# pcie_board.net
KiCad netlist of a schematic drawn in EAGLE
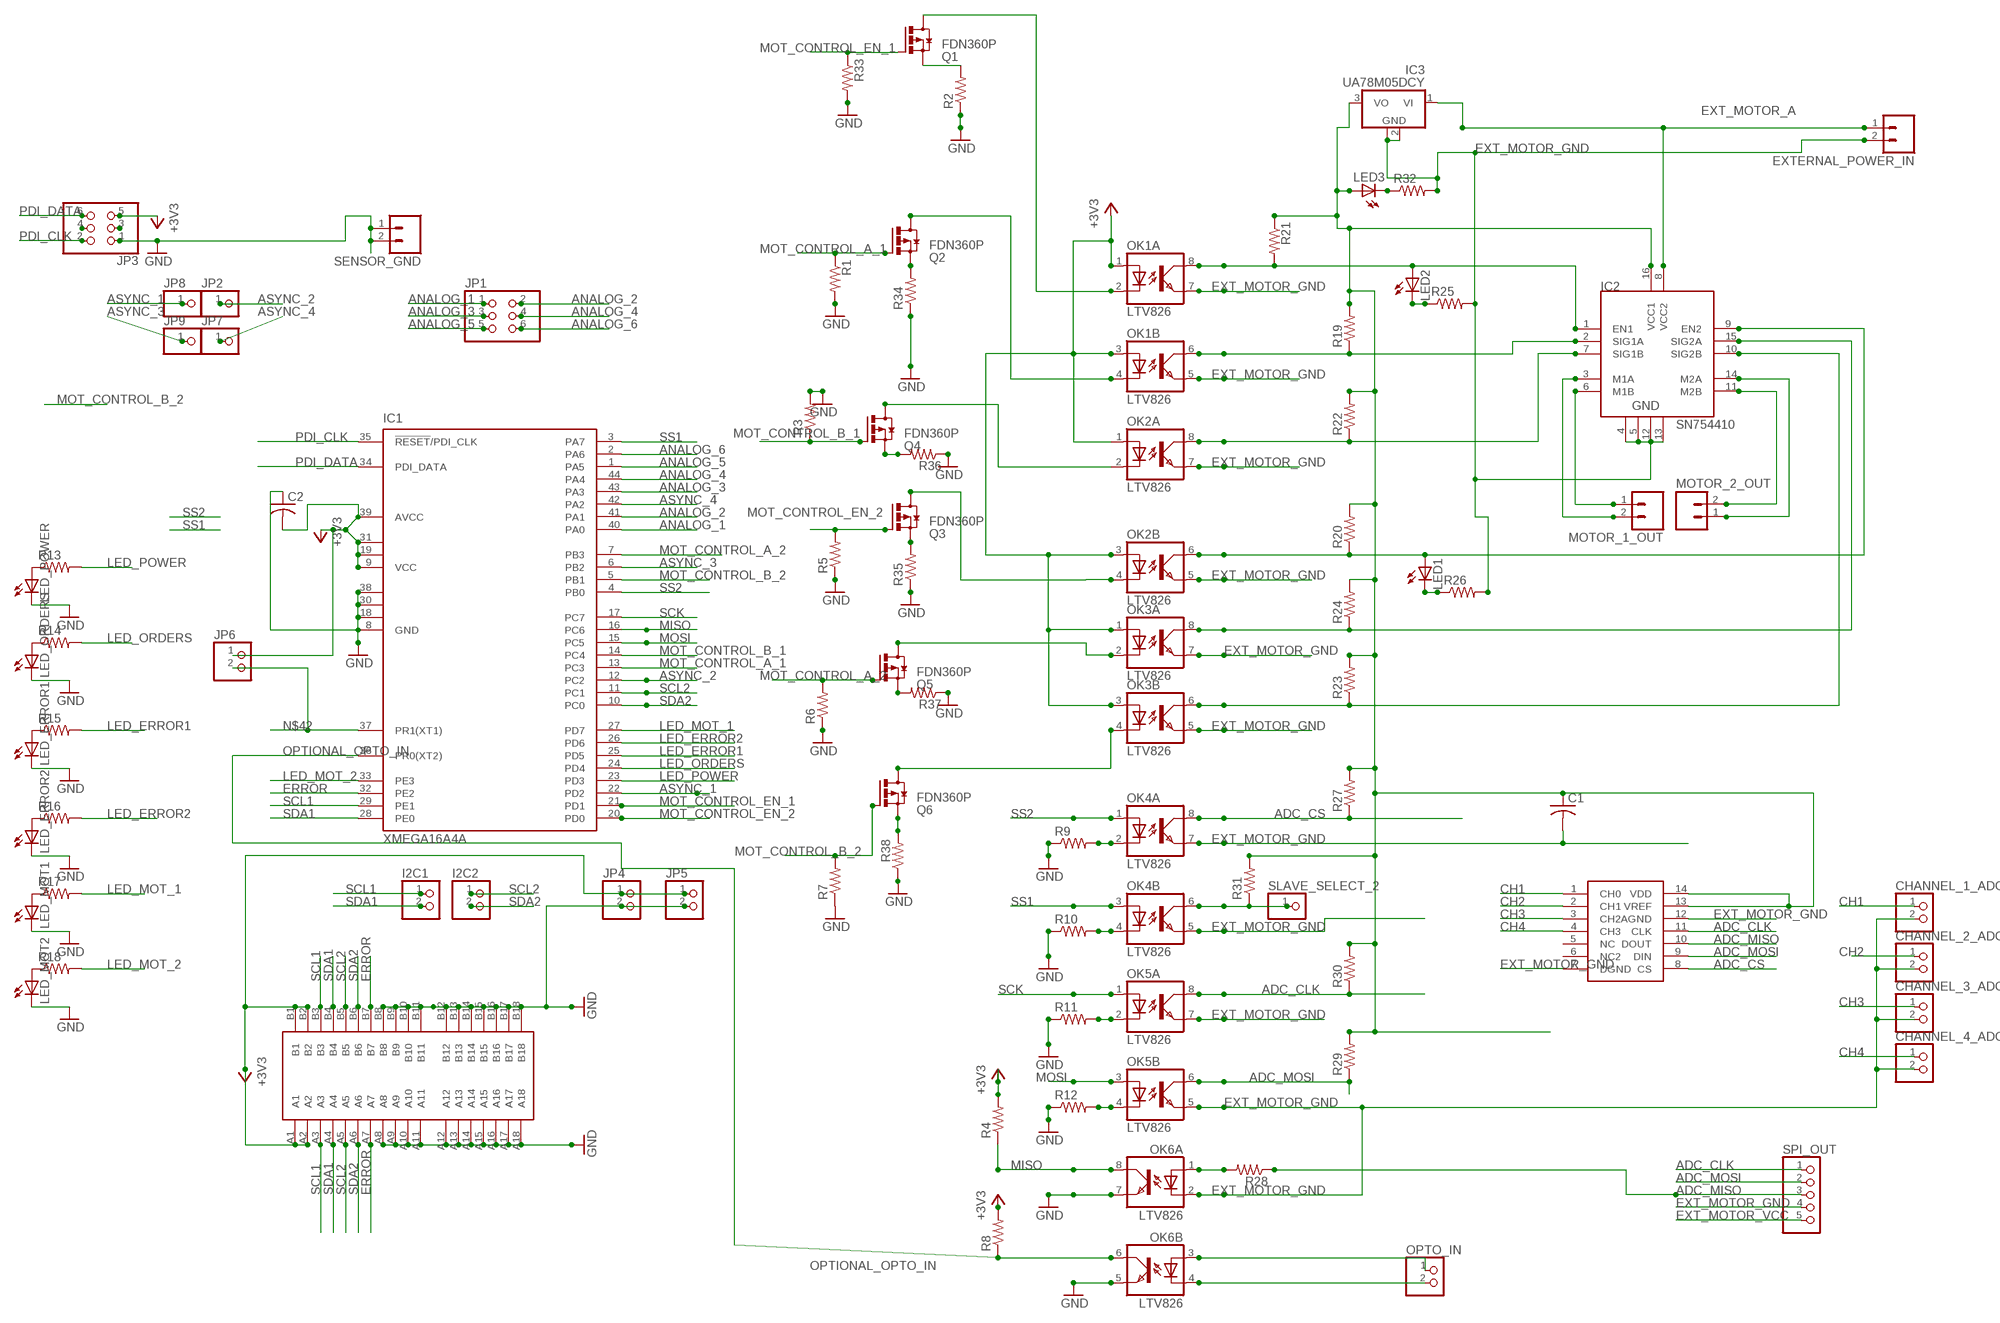
[diagram p0: schematic, sheet 1]

(export (version "E")
  (design (tool "Eeschema 10.0.6"))
  (components
    (comp (ref "C1")
      (value "C-US025-040X050")
      (footprint "eagle-import:C025-040X050")
      (libsource (lib "eagle-import") (part "C-US025-040X050"))
    )
    (comp (ref "C2")
      (value "C-US025-040X050")
      (footprint "eagle-import:C025-040X050")
      (libsource (lib "eagle-import") (part "C-US025-040X050"))
    )
    (comp (ref "CHANNEL_1_ADC")
      (value "PINHD-1X2")
      (footprint "eagle-import:1X02")
      (libsource (lib "eagle-import") (part "PINHD-1X2"))
    )
    (comp (ref "CHANNEL_2_ADC")
      (value "PINHD-1X2")
      (footprint "eagle-import:1X02")
      (libsource (lib "eagle-import") (part "PINHD-1X2"))
    )
    (comp (ref "CHANNEL_3_ADC")
      (value "PINHD-1X2")
      (footprint "eagle-import:1X02")
      (libsource (lib "eagle-import") (part "PINHD-1X2"))
    )
    (comp (ref "CHANNEL_4_ADC")
      (value "PINHD-1X2")
      (footprint "eagle-import:1X02")
      (libsource (lib "eagle-import") (part "PINHD-1X2"))
    )
    (comp (ref "EXTERNAL_POWER_IN")
      (value "M023.5MM")
      (footprint "eagle-import:SCREWTERMINAL-3.5MM-2")
      (libsource (lib "eagle-import") (part "M023.5MM"))
    )
    (comp (ref "I2C1")
      (value "PINHD-1X2")
      (footprint "eagle-import:1X02")
      (libsource (lib "eagle-import") (part "PINHD-1X2"))
    )
    (comp (ref "I2C2")
      (value "PINHD-1X2")
      (footprint "eagle-import:1X02")
      (libsource (lib "eagle-import") (part "PINHD-1X2"))
    )
    (comp (ref "IC1")
      (value "XMEGA16A4A")
      (footprint "eagle-import:TQFP44")
      (libsource (lib "eagle-import") (part "XMEGA16A4A"))
    )
    (comp (ref "IC2")
      (value "SN754410")
      (footprint "eagle-import:DIP16")
      (libsource (lib "eagle-import") (part "SN754410"))
    )
    (comp (ref "IC3")
      (value "UA78M05DCY")
      (footprint "eagle-import:SOT223")
      (libsource (lib "eagle-import") (part "UA78MDCY05"))
    )
    (comp (ref "JP1")
      (value "PINHD-2X3")
      (footprint "eagle-import:2X03")
      (libsource (lib "eagle-import") (part "PINHD-2X3"))
    )
    (comp (ref "JP2")
      (value "PINHD-1X1")
      (footprint "eagle-import:1X01")
      (libsource (lib "eagle-import") (part "PINHD-1X1"))
    )
    (comp (ref "JP3")
      (value "PINHD-2X3")
      (footprint "eagle-import:2X03")
      (libsource (lib "eagle-import") (part "PINHD-2X3"))
    )
    (comp (ref "JP4")
      (value "PINHD-1X2")
      (footprint "eagle-import:1X02")
      (libsource (lib "eagle-import") (part "PINHD-1X2"))
    )
    (comp (ref "JP5")
      (value "PINHD-1X2")
      (footprint "eagle-import:1X02")
      (libsource (lib "eagle-import") (part "PINHD-1X2"))
    )
    (comp (ref "JP6")
      (value "PINHD-1X2")
      (footprint "eagle-import:1X02")
      (libsource (lib "eagle-import") (part "PINHD-1X2"))
    )
    (comp (ref "JP7")
      (value "PINHD-1X1")
      (footprint "eagle-import:1X01")
      (libsource (lib "eagle-import") (part "PINHD-1X1"))
    )
    (comp (ref "JP8")
      (value "PINHD-1X1")
      (footprint "eagle-import:1X01")
      (libsource (lib "eagle-import") (part "PINHD-1X1"))
    )
    (comp (ref "JP9")
      (value "PINHD-1X1")
      (footprint "eagle-import:1X01")
      (libsource (lib "eagle-import") (part "PINHD-1X1"))
    )
    (comp (ref "LED1")
      (value "LEDCHIP-LED0603")
      (footprint "eagle-import:CHIP-LED0603")
      (libsource (lib "eagle-import") (part "LEDCHIP-LED0603"))
    )
    (comp (ref "LED2")
      (value "LEDCHIP-LED0603")
      (footprint "eagle-import:CHIP-LED0603")
      (libsource (lib "eagle-import") (part "LEDCHIP-LED0603"))
    )
    (comp (ref "LED3")
      (value "LEDCHIP-LED0603")
      (footprint "eagle-import:CHIP-LED0603")
      (libsource (lib "eagle-import") (part "LEDCHIP-LED0603"))
    )
    (comp (ref "LED_ERROR1")
      (value "LED5MM")
      (footprint "eagle-import:LED5MM")
      (libsource (lib "eagle-import") (part "LED5MM"))
    )
    (comp (ref "LED_ERROR2")
      (value "LED5MM")
      (footprint "eagle-import:LED5MM")
      (libsource (lib "eagle-import") (part "LED5MM"))
    )
    (comp (ref "LED_MOT1")
      (value "LED5MM")
      (footprint "eagle-import:LED5MM")
      (libsource (lib "eagle-import") (part "LED5MM"))
    )
    (comp (ref "LED_MOT2")
      (value "LED5MM")
      (footprint "eagle-import:LED5MM")
      (libsource (lib "eagle-import") (part "LED5MM"))
    )
    (comp (ref "LED_ORDERS")
      (value "LED5MM")
      (footprint "eagle-import:LED5MM")
      (libsource (lib "eagle-import") (part "LED5MM"))
    )
    (comp (ref "LED_POWER")
      (value "LED5MM")
      (footprint "eagle-import:LED5MM")
      (libsource (lib "eagle-import") (part "LED5MM"))
    )
    (comp (ref "MOTOR_1_OUT")
      (value "M023.5MM")
      (footprint "eagle-import:SCREWTERMINAL-3.5MM-2")
      (libsource (lib "eagle-import") (part "M023.5MM"))
    )
    (comp (ref "MOTOR_2_OUT")
      (value "M023.5MM")
      (footprint "eagle-import:SCREWTERMINAL-3.5MM-2")
      (libsource (lib "eagle-import") (part "M023.5MM"))
    )
    (comp (ref "OK1")
      (value "LTV826")
      (footprint "eagle-import:DIL08")
      (libsource (lib "eagle-import") (part "LTV826"))
    )
    (comp (ref "OK2")
      (value "LTV826")
      (footprint "eagle-import:DIL08")
      (libsource (lib "eagle-import") (part "LTV826"))
    )
    (comp (ref "OK3")
      (value "LTV826")
      (footprint "eagle-import:DIL08")
      (libsource (lib "eagle-import") (part "LTV826"))
    )
    (comp (ref "OK4")
      (value "LTV826")
      (footprint "eagle-import:DIL08")
      (libsource (lib "eagle-import") (part "LTV826"))
    )
    (comp (ref "OK5")
      (value "LTV826")
      (footprint "eagle-import:DIL08")
      (libsource (lib "eagle-import") (part "LTV826"))
    )
    (comp (ref "OK6")
      (value "LTV826")
      (footprint "eagle-import:DIL08")
      (libsource (lib "eagle-import") (part "LTV826"))
    )
    (comp (ref "OPTO_IN")
      (value "PINHD-1X2")
      (footprint "eagle-import:1X02")
      (libsource (lib "eagle-import") (part "PINHD-1X2"))
    )
    (comp (ref "Q1")
      (value "FDN360P")
      (footprint "eagle-import:SUPER-SOT3")
      (libsource (lib "eagle-import") (part "FDN360P"))
    )
    (comp (ref "Q2")
      (value "FDN360P")
      (footprint "eagle-import:SUPER-SOT3")
      (libsource (lib "eagle-import") (part "FDN360P"))
    )
    (comp (ref "Q3")
      (value "FDN360P")
      (footprint "eagle-import:SUPER-SOT3")
      (libsource (lib "eagle-import") (part "FDN360P"))
    )
    (comp (ref "Q4")
      (value "FDN360P")
      (footprint "eagle-import:SUPER-SOT3")
      (libsource (lib "eagle-import") (part "FDN360P"))
    )
    (comp (ref "Q5")
      (value "FDN360P")
      (footprint "eagle-import:SUPER-SOT3")
      (libsource (lib "eagle-import") (part "FDN360P"))
    )
    (comp (ref "Q6")
      (value "FDN360P")
      (footprint "eagle-import:SUPER-SOT3")
      (libsource (lib "eagle-import") (part "FDN360P"))
    )
    (comp (ref "R1")
      (value "R-US_M0805")
      (footprint "eagle-import:M0805")
      (libsource (lib "eagle-import") (part "R-US_M0805"))
    )
    (comp (ref "R2")
      (value "R-US_M0805")
      (footprint "eagle-import:M0805")
      (libsource (lib "eagle-import") (part "R-US_M0805"))
    )
    (comp (ref "R3")
      (value "R-US_M0805")
      (footprint "eagle-import:M0805")
      (libsource (lib "eagle-import") (part "R-US_M0805"))
    )
    (comp (ref "R4")
      (value "R-US_M0805")
      (footprint "eagle-import:M0805")
      (libsource (lib "eagle-import") (part "R-US_M0805"))
    )
    (comp (ref "R5")
      (value "R-US_M0805")
      (footprint "eagle-import:M0805")
      (libsource (lib "eagle-import") (part "R-US_M0805"))
    )
    (comp (ref "R6")
      (value "R-US_M0805")
      (footprint "eagle-import:M0805")
      (libsource (lib "eagle-import") (part "R-US_M0805"))
    )
    (comp (ref "R7")
      (value "R-US_M0805")
      (footprint "eagle-import:M0805")
      (libsource (lib "eagle-import") (part "R-US_M0805"))
    )
    (comp (ref "R8")
      (value "R-US_M0805")
      (footprint "eagle-import:M0805")
      (libsource (lib "eagle-import") (part "R-US_M0805"))
    )
    (comp (ref "R9")
      (value "R-US_M0805")
      (footprint "eagle-import:M0805")
      (libsource (lib "eagle-import") (part "R-US_M0805"))
    )
    (comp (ref "R10")
      (value "R-US_M0805")
      (footprint "eagle-import:M0805")
      (libsource (lib "eagle-import") (part "R-US_M0805"))
    )
    (comp (ref "R11")
      (value "R-US_M0805")
      (footprint "eagle-import:M0805")
      (libsource (lib "eagle-import") (part "R-US_M0805"))
    )
    (comp (ref "R12")
      (value "R-US_M0805")
      (footprint "eagle-import:M0805")
      (libsource (lib "eagle-import") (part "R-US_M0805"))
    )
    (comp (ref "R13")
      (value "R-US_M0805")
      (footprint "eagle-import:M0805")
      (libsource (lib "eagle-import") (part "R-US_M0805"))
    )
    (comp (ref "R14")
      (value "R-US_M0805")
      (footprint "eagle-import:M0805")
      (libsource (lib "eagle-import") (part "R-US_M0805"))
    )
    (comp (ref "R15")
      (value "R-US_M0805")
      (footprint "eagle-import:M0805")
      (libsource (lib "eagle-import") (part "R-US_M0805"))
    )
    (comp (ref "R16")
      (value "R-US_M0805")
      (footprint "eagle-import:M0805")
      (libsource (lib "eagle-import") (part "R-US_M0805"))
    )
    (comp (ref "R17")
      (value "R-US_M0805")
      (footprint "eagle-import:M0805")
      (libsource (lib "eagle-import") (part "R-US_M0805"))
    )
    (comp (ref "R18")
      (value "R-US_M0805")
      (footprint "eagle-import:M0805")
      (libsource (lib "eagle-import") (part "R-US_M0805"))
    )
    (comp (ref "R19")
      (value "R-US_M0805")
      (footprint "eagle-import:M0805")
      (libsource (lib "eagle-import") (part "R-US_M0805"))
    )
    (comp (ref "R20")
      (value "R-US_M0805")
      (footprint "eagle-import:M0805")
      (libsource (lib "eagle-import") (part "R-US_M0805"))
    )
    (comp (ref "R21")
      (value "R-US_M0805")
      (footprint "eagle-import:M0805")
      (libsource (lib "eagle-import") (part "R-US_M0805"))
    )
    (comp (ref "R22")
      (value "R-US_M0805")
      (footprint "eagle-import:M0805")
      (libsource (lib "eagle-import") (part "R-US_M0805"))
    )
    (comp (ref "R23")
      (value "R-US_M0805")
      (footprint "eagle-import:M0805")
      (libsource (lib "eagle-import") (part "R-US_M0805"))
    )
    (comp (ref "R24")
      (value "R-US_M0805")
      (footprint "eagle-import:M0805")
      (libsource (lib "eagle-import") (part "R-US_M0805"))
    )
    (comp (ref "R25")
      (value "R-US_M0805")
      (footprint "eagle-import:M0805")
      (libsource (lib "eagle-import") (part "R-US_M0805"))
    )
    (comp (ref "R26")
      (value "R-US_M0805")
      (footprint "eagle-import:M0805")
      (libsource (lib "eagle-import") (part "R-US_M0805"))
    )
    (comp (ref "R27")
      (value "R-US_M0805")
      (footprint "eagle-import:M0805")
      (libsource (lib "eagle-import") (part "R-US_M0805"))
    )
    (comp (ref "R28")
      (value "R-US_M0805")
      (footprint "eagle-import:M0805")
      (libsource (lib "eagle-import") (part "R-US_M0805"))
    )
    (comp (ref "R29")
      (value "R-US_M0805")
      (footprint "eagle-import:M0805")
      (libsource (lib "eagle-import") (part "R-US_M0805"))
    )
    (comp (ref "R30")
      (value "R-US_M0805")
      (footprint "eagle-import:M0805")
      (libsource (lib "eagle-import") (part "R-US_M0805"))
    )
    (comp (ref "R31")
      (value "R-US_M0805")
      (footprint "eagle-import:M0805")
      (libsource (lib "eagle-import") (part "R-US_M0805"))
    )
    (comp (ref "R32")
      (value "R-US_M0805")
      (footprint "eagle-import:M0805")
      (libsource (lib "eagle-import") (part "R-US_M0805"))
    )
    (comp (ref "R33")
      (value "R-US_M0805")
      (footprint "eagle-import:M0805")
      (libsource (lib "eagle-import") (part "R-US_M0805"))
    )
    (comp (ref "R34")
      (value "R-US_M0805")
      (footprint "eagle-import:M0805")
      (libsource (lib "eagle-import") (part "R-US_M0805"))
    )
    (comp (ref "R35")
      (value "R-US_M0805")
      (footprint "eagle-import:M0805")
      (libsource (lib "eagle-import") (part "R-US_M0805"))
    )
    (comp (ref "R36")
      (value "R-US_M0805")
      (footprint "eagle-import:M0805")
      (libsource (lib "eagle-import") (part "R-US_M0805"))
    )
    (comp (ref "R37")
      (value "R-US_M0805")
      (footprint "eagle-import:M0805")
      (libsource (lib "eagle-import") (part "R-US_M0805"))
    )
    (comp (ref "R38")
      (value "R-US_M0805")
      (footprint "eagle-import:M0805")
      (libsource (lib "eagle-import") (part "R-US_M0805"))
    )
    (comp (ref "SENSOR_GND")
      (value "M023.5MM")
      (footprint "eagle-import:SCREWTERMINAL-3.5MM-2")
      (libsource (lib "eagle-import") (part "M023.5MM"))
    )
    (comp (ref "SLAVE_SELECT_2")
      (value "PINHD-1X1")
      (footprint "eagle-import:1X01")
      (libsource (lib "eagle-import") (part "PINHD-1X1"))
    )
    (comp (ref "SPI_OUT")
      (value "PINHD-1X5")
      (footprint "eagle-import:1X05")
      (libsource (lib "eagle-import") (part "PINHD-1X5"))
    )
    (comp (ref "U$1")
      (value "PCI-E1X_EDGE")
      (footprint "eagle-import:PCI-E_X1_EDGE")
      (libsource (lib "eagle-import") (part "PCI-E1X_EDGE"))
    )
    (comp (ref "U$2")
      (value "MCP3004")
      (footprint "eagle-import:DIL14")
      (libsource (lib "eagle-import") (part "MCP3004"))
    )
  )
  (nets
    (net (code "1") (name "+3V3") (class "Default")
      (node (ref "C2") (pin "2") (pinfunction "2_2") (pintype "passive"))
      (node (ref "IC1") (pin "19") (pinfunction "VCC1_19") (pintype "power_in"))
      (node (ref "IC1") (pin "31") (pinfunction "VCC2_31") (pintype "power_in"))
      (node (ref "IC1") (pin "39") (pinfunction "AVCC_39") (pintype "power_in"))
      (node (ref "IC1") (pin "9") (pinfunction "VCC_9") (pintype "power_in"))
      (node (ref "JP3") (pin "5") (pinfunction "5_5") (pintype "passive"))
      (node (ref "JP4") (pin "1") (pinfunction "1_1") (pintype "passive"))
      (node (ref "JP5") (pin "1") (pinfunction "1_1") (pintype "passive"))
      (node (ref "JP6") (pin "1") (pinfunction "1_1") (pintype "passive"))
      (node (ref "OK1") (pin "1") (pinfunction "A_1") (pintype "passive"))
      (node (ref "OK1") (pin "3") (pinfunction "A_3") (pintype "passive"))
      (node (ref "OK2") (pin "1") (pinfunction "A_1") (pintype "passive"))
      (node (ref "OK2") (pin "3") (pinfunction "A_3") (pintype "passive"))
      (node (ref "OK3") (pin "1") (pinfunction "A_1") (pintype "passive"))
      (node (ref "OK3") (pin "3") (pinfunction "A_3") (pintype "passive"))
      (node (ref "R4") (pin "2") (pinfunction "2_2") (pintype "passive"))
      (node (ref "R8") (pin "2") (pinfunction "2_2") (pintype "passive"))
      (node (ref "U$1") (pin "A1") (pinfunction "A1_A1") (pintype "bidirectional"))
      (node (ref "U$1") (pin "A2") (pinfunction "A2_A2") (pintype "bidirectional"))
      (node (ref "U$1") (pin "B1") (pinfunction "B1_B1") (pintype "bidirectional"))
      (node (ref "U$1") (pin "B2") (pinfunction "B2_B2") (pintype "bidirectional"))
    )
    (net (code "2") (name "ADC_CLK") (class "Default")
      (node (ref "OK5") (pin "8") (pinfunction "COL_8") (pintype "passive"))
      (node (ref "R30") (pin "1") (pinfunction "1_1") (pintype "passive"))
      (node (ref "SPI_OUT") (pin "1") (pinfunction "1_1") (pintype "passive"))
      (node (ref "U$2") (pin "11") (pinfunction "CLK_11") (pintype "bidirectional"))
    )
    (net (code "3") (name "ADC_CS") (class "Default")
      (node (ref "OK4") (pin "8") (pinfunction "COL_8") (pintype "passive"))
      (node (ref "R27") (pin "1") (pinfunction "1_1") (pintype "passive"))
      (node (ref "U$2") (pin "8") (pinfunction "CS_8") (pintype "bidirectional"))
    )
    (net (code "4") (name "ADC_MISO") (class "Default")
      (node (ref "R28") (pin "1") (pinfunction "1_1") (pintype "passive"))
      (node (ref "SPI_OUT") (pin "3") (pinfunction "3_3") (pintype "passive"))
      (node (ref "U$2") (pin "10") (pinfunction "DOUT_10") (pintype "bidirectional"))
    )
    (net (code "5") (name "ADC_MOSI") (class "Default")
      (node (ref "OK5") (pin "6") (pinfunction "COL_6") (pintype "passive"))
      (node (ref "R29") (pin "1") (pinfunction "1_1") (pintype "passive"))
      (node (ref "SPI_OUT") (pin "2") (pinfunction "2_2") (pintype "passive"))
      (node (ref "U$2") (pin "9") (pinfunction "DIN_9") (pintype "bidirectional"))
    )
    (net (code "6") (name "ANALOG_1") (class "Default")
      (node (ref "IC1") (pin "40") (pinfunction "PA0_40") (pintype "bidirectional"))
      (node (ref "JP1") (pin "1") (pinfunction "1_1") (pintype "passive"))
    )
    (net (code "7") (name "ANALOG_2") (class "Default")
      (node (ref "IC1") (pin "41") (pinfunction "PA1_41") (pintype "bidirectional"))
      (node (ref "JP1") (pin "2") (pinfunction "2_2") (pintype "passive"))
    )
    (net (code "8") (name "ANALOG_3") (class "Default")
      (node (ref "IC1") (pin "43") (pinfunction "PA3_43") (pintype "bidirectional"))
      (node (ref "JP1") (pin "3") (pinfunction "3_3") (pintype "passive"))
    )
    (net (code "9") (name "ANALOG_4") (class "Default")
      (node (ref "IC1") (pin "44") (pinfunction "PA4_44") (pintype "bidirectional"))
      (node (ref "JP1") (pin "4") (pinfunction "4_4") (pintype "passive"))
    )
    (net (code "10") (name "ANALOG_5") (class "Default")
      (node (ref "IC1") (pin "1") (pinfunction "PA5_1") (pintype "bidirectional"))
      (node (ref "JP1") (pin "5") (pinfunction "5_5") (pintype "passive"))
    )
    (net (code "11") (name "ANALOG_6") (class "Default")
      (node (ref "IC1") (pin "2") (pinfunction "PA6_2") (pintype "bidirectional"))
      (node (ref "JP1") (pin "6") (pinfunction "6_6") (pintype "passive"))
    )
    (net (code "12") (name "ASYNC_1") (class "Default")
      (node (ref "IC1") (pin "22") (pinfunction "PD2_22") (pintype "bidirectional"))
      (node (ref "JP8") (pin "1") (pinfunction "1_1") (pintype "passive"))
    )
    (net (code "13") (name "ASYNC_2") (class "Default")
      (node (ref "IC1") (pin "12") (pinfunction "PC2_12") (pintype "bidirectional"))
      (node (ref "JP2") (pin "1") (pinfunction "1_1") (pintype "passive"))
    )
    (net (code "14") (name "ASYNC_3") (class "Default")
      (node (ref "IC1") (pin "6") (pinfunction "PB2_6") (pintype "bidirectional"))
      (node (ref "JP9") (pin "1") (pinfunction "1_1") (pintype "passive"))
    )
    (net (code "15") (name "ASYNC_4") (class "Default")
      (node (ref "IC1") (pin "42") (pinfunction "PA2_42") (pintype "bidirectional"))
      (node (ref "JP7") (pin "1") (pinfunction "1_1") (pintype "passive"))
    )
    (net (code "16") (name "CH1") (class "Default")
      (node (ref "CHANNEL_1_ADC") (pin "1") (pinfunction "1_1") (pintype "passive"))
      (node (ref "U$2") (pin "1") (pinfunction "CH0_1") (pintype "bidirectional"))
    )
    (net (code "17") (name "CH2") (class "Default")
      (node (ref "CHANNEL_2_ADC") (pin "1") (pinfunction "1_1") (pintype "passive"))
      (node (ref "U$2") (pin "2") (pinfunction "CH1_2") (pintype "bidirectional"))
    )
    (net (code "18") (name "CH3") (class "Default")
      (node (ref "CHANNEL_3_ADC") (pin "1") (pinfunction "1_1") (pintype "passive"))
      (node (ref "U$2") (pin "3") (pinfunction "CH2_3") (pintype "bidirectional"))
    )
    (net (code "19") (name "CH4") (class "Default")
      (node (ref "CHANNEL_4_ADC") (pin "1") (pinfunction "1_1") (pintype "passive"))
      (node (ref "U$2") (pin "4") (pinfunction "CH3_4") (pintype "bidirectional"))
    )
    (net (code "20") (name "ERROR") (class "Default")
      (node (ref "IC1") (pin "32") (pinfunction "PE2_32") (pintype "bidirectional"))
      (node (ref "U$1") (pin "A7") (pinfunction "A7_A7") (pintype "bidirectional"))
      (node (ref "U$1") (pin "B7") (pinfunction "B7_B7") (pintype "bidirectional"))
    )
    (net (code "21") (name "EXT_MOTOR_A") (class "Default")
      (node (ref "EXTERNAL_POWER_IN") (pin "1") (pinfunction "1_1") (pintype "passive"))
      (node (ref "IC2") (pin "8") (pinfunction "VCC2_8") (pintype "power_in"))
      (node (ref "IC3") (pin "1") (pinfunction "VI_1") (pintype "input"))
    )
    (net (code "22") (name "EXT_MOTOR_GND") (class "Default")
      (node (ref "C1") (pin "2") (pinfunction "2_2") (pintype "passive"))
      (node (ref "CHANNEL_1_ADC") (pin "2") (pinfunction "2_2") (pintype "passive"))
      (node (ref "CHANNEL_2_ADC") (pin "2") (pinfunction "2_2") (pintype "passive"))
      (node (ref "CHANNEL_3_ADC") (pin "2") (pinfunction "2_2") (pintype "passive"))
      (node (ref "CHANNEL_4_ADC") (pin "2") (pinfunction "2_2") (pintype "passive"))
      (node (ref "EXTERNAL_POWER_IN") (pin "2") (pinfunction "2_2") (pintype "passive"))
      (node (ref "IC2") (pin "12") (pinfunction "P12_12") (pintype "power_in"))
      (node (ref "IC2") (pin "13") (pinfunction "P13_13") (pintype "power_in"))
      (node (ref "IC2") (pin "4") (pinfunction "P4_4") (pintype "power_in"))
      (node (ref "IC2") (pin "5") (pinfunction "P5_5") (pintype "power_in"))
      (node (ref "IC3") (pin "2") (pinfunction "GND_2") (pintype "passive"))
      (node (ref "IC3") (pin "4") (pinfunction "GND_4") (pintype "passive"))
      (node (ref "OK1") (pin "5") (pinfunction "EMIT_5") (pintype "passive"))
      (node (ref "OK1") (pin "7") (pinfunction "EMIT_7") (pintype "passive"))
      (node (ref "OK2") (pin "5") (pinfunction "EMIT_5") (pintype "passive"))
      (node (ref "OK2") (pin "7") (pinfunction "EMIT_7") (pintype "passive"))
      (node (ref "OK3") (pin "5") (pinfunction "EMIT_5") (pintype "passive"))
      (node (ref "OK3") (pin "7") (pinfunction "EMIT_7") (pintype "passive"))
      (node (ref "OK4") (pin "5") (pinfunction "EMIT_5") (pintype "passive"))
      (node (ref "OK4") (pin "7") (pinfunction "EMIT_7") (pintype "passive"))
      (node (ref "OK5") (pin "5") (pinfunction "EMIT_5") (pintype "passive"))
      (node (ref "OK5") (pin "7") (pinfunction "EMIT_7") (pintype "passive"))
      (node (ref "OK6") (pin "2") (pinfunction "C_2") (pintype "passive"))
      (node (ref "R25") (pin "2") (pinfunction "2_2") (pintype "passive"))
      (node (ref "R26") (pin "2") (pinfunction "2_2") (pintype "passive"))
      (node (ref "R32") (pin "2") (pinfunction "2_2") (pintype "passive"))
      (node (ref "SPI_OUT") (pin "4") (pinfunction "4_4") (pintype "passive"))
      (node (ref "U$2") (pin "12") (pinfunction "AGND_12") (pintype "bidirectional"))
      (node (ref "U$2") (pin "7") (pinfunction "DGND_7") (pintype "bidirectional"))
    )
    (net (code "23") (name "EXT_MOTOR_VCC") (class "Default")
      (node (ref "C1") (pin "1") (pinfunction "1_1") (pintype "passive"))
      (node (ref "IC2") (pin "16") (pinfunction "VCC1_16") (pintype "power_in"))
      (node (ref "IC3") (pin "3") (pinfunction "VO_3") (pintype "passive"))
      (node (ref "LED3") (pin "A") (pinfunction "A_A") (pintype "passive"))
      (node (ref "R19") (pin "2") (pinfunction "2_2") (pintype "passive"))
      (node (ref "R20") (pin "2") (pinfunction "2_2") (pintype "passive"))
      (node (ref "R21") (pin "1") (pinfunction "1_1") (pintype "passive"))
      (node (ref "R22") (pin "2") (pinfunction "2_2") (pintype "passive"))
      (node (ref "R23") (pin "2") (pinfunction "2_2") (pintype "passive"))
      (node (ref "R24") (pin "2") (pinfunction "2_2") (pintype "passive"))
      (node (ref "R27") (pin "2") (pinfunction "2_2") (pintype "passive"))
      (node (ref "R29") (pin "2") (pinfunction "2_2") (pintype "passive"))
      (node (ref "R30") (pin "2") (pinfunction "2_2") (pintype "passive"))
      (node (ref "R31") (pin "2") (pinfunction "2_2") (pintype "passive"))
      (node (ref "SPI_OUT") (pin "5") (pinfunction "5_5") (pintype "passive"))
      (node (ref "U$2") (pin "13") (pinfunction "VREF_13") (pintype "bidirectional"))
      (node (ref "U$2") (pin "14") (pinfunction "VDD_14") (pintype "bidirectional"))
    )
    (net (code "24") (name "GND") (class "Default")
      (node (ref "C2") (pin "1") (pinfunction "1_1") (pintype "passive"))
      (node (ref "IC1") (pin "18") (pinfunction "GND1_18") (pintype "power_in"))
      (node (ref "IC1") (pin "30") (pinfunction "GND2_30") (pintype "power_in"))
      (node (ref "IC1") (pin "38") (pinfunction "GND3_38") (pintype "power_in"))
      (node (ref "IC1") (pin "8") (pinfunction "GND_8") (pintype "power_in"))
      (node (ref "JP3") (pin "1") (pinfunction "1_1") (pintype "passive"))
      (node (ref "JP4") (pin "2") (pinfunction "2_2") (pintype "passive"))
      (node (ref "JP5") (pin "2") (pinfunction "2_2") (pintype "passive"))
      (node (ref "LED_ERROR1") (pin "K") (pinfunction "C_K") (pintype "passive"))
      (node (ref "LED_ERROR2") (pin "K") (pinfunction "C_K") (pintype "passive"))
      (node (ref "LED_MOT1") (pin "K") (pinfunction "C_K") (pintype "passive"))
      (node (ref "LED_MOT2") (pin "K") (pinfunction "C_K") (pintype "passive"))
      (node (ref "LED_ORDERS") (pin "K") (pinfunction "C_K") (pintype "passive"))
      (node (ref "LED_POWER") (pin "K") (pinfunction "C_K") (pintype "passive"))
      (node (ref "OK6") (pin "5") (pinfunction "EMIT_5") (pintype "passive"))
      (node (ref "OK6") (pin "7") (pinfunction "EMIT_7") (pintype "passive"))
      (node (ref "R1") (pin "2") (pinfunction "2_2") (pintype "passive"))
      (node (ref "R10") (pin "1") (pinfunction "1_1") (pintype "passive"))
      (node (ref "R11") (pin "1") (pinfunction "1_1") (pintype "passive"))
      (node (ref "R12") (pin "1") (pinfunction "1_1") (pintype "passive"))
      (node (ref "R2") (pin "1") (pinfunction "1_1") (pintype "passive"))
      (node (ref "R3") (pin "2") (pinfunction "2_2") (pintype "passive"))
      (node (ref "R33") (pin "2") (pinfunction "2_2") (pintype "passive"))
      (node (ref "R34") (pin "1") (pinfunction "1_1") (pintype "passive"))
      (node (ref "R35") (pin "1") (pinfunction "1_1") (pintype "passive"))
      (node (ref "R36") (pin "1") (pinfunction "1_1") (pintype "passive"))
      (node (ref "R37") (pin "1") (pinfunction "1_1") (pintype "passive"))
      (node (ref "R38") (pin "1") (pinfunction "1_1") (pintype "passive"))
      (node (ref "R5") (pin "1") (pinfunction "1_1") (pintype "passive"))
      (node (ref "R6") (pin "1") (pinfunction "1_1") (pintype "passive"))
      (node (ref "R7") (pin "1") (pinfunction "1_1") (pintype "passive"))
      (node (ref "R9") (pin "1") (pinfunction "1_1") (pintype "passive"))
      (node (ref "SENSOR_GND") (pin "1") (pinfunction "1_1") (pintype "passive"))
      (node (ref "SENSOR_GND") (pin "2") (pinfunction "2_2") (pintype "passive"))
      (node (ref "U$1") (pin "A10") (pinfunction "A10_A10") (pintype "bidirectional"))
      (node (ref "U$1") (pin "A11") (pinfunction "A11_A11") (pintype "bidirectional"))
      (node (ref "U$1") (pin "A12") (pinfunction "A12_A12") (pintype "bidirectional"))
      (node (ref "U$1") (pin "A13") (pinfunction "A13_A13") (pintype "bidirectional"))
      (node (ref "U$1") (pin "A14") (pinfunction "A14_A14") (pintype "bidirectional"))
      (node (ref "U$1") (pin "A15") (pinfunction "A15_A15") (pintype "bidirectional"))
      (node (ref "U$1") (pin "A16") (pinfunction "A16_A16") (pintype "bidirectional"))
      (node (ref "U$1") (pin "A17") (pinfunction "A17_A17") (pintype "bidirectional"))
      (node (ref "U$1") (pin "A18") (pinfunction "A18_A18") (pintype "bidirectional"))
      (node (ref "U$1") (pin "A8") (pinfunction "A8_A8") (pintype "bidirectional"))
      (node (ref "U$1") (pin "A9") (pinfunction "A9_A9") (pintype "bidirectional"))
      (node (ref "U$1") (pin "B10") (pinfunction "B10_B10") (pintype "bidirectional"))
      (node (ref "U$1") (pin "B11") (pinfunction "B11_B11") (pintype "bidirectional"))
      (node (ref "U$1") (pin "B12") (pinfunction "B12_B12") (pintype "bidirectional"))
      (node (ref "U$1") (pin "B13") (pinfunction "B13_B13") (pintype "bidirectional"))
      (node (ref "U$1") (pin "B14") (pinfunction "B14_B14") (pintype "bidirectional"))
      (node (ref "U$1") (pin "B15") (pinfunction "B15_B15") (pintype "bidirectional"))
      (node (ref "U$1") (pin "B16") (pinfunction "B16_B16") (pintype "bidirectional"))
      (node (ref "U$1") (pin "B17") (pinfunction "B17_B17") (pintype "bidirectional"))
      (node (ref "U$1") (pin "B18") (pinfunction "B18_B18") (pintype "bidirectional"))
      (node (ref "U$1") (pin "B8") (pinfunction "B8_B8") (pintype "bidirectional"))
      (node (ref "U$1") (pin "B9") (pinfunction "B9_B9") (pintype "bidirectional"))
    )
    (net (code "25") (name "LED_ERROR1") (class "Default")
      (node (ref "IC1") (pin "25") (pinfunction "PD5_25") (pintype "bidirectional"))
      (node (ref "R15") (pin "2") (pinfunction "2_2") (pintype "passive"))
    )
    (net (code "26") (name "LED_ERROR2") (class "Default")
      (node (ref "IC1") (pin "26") (pinfunction "PD6_26") (pintype "bidirectional"))
      (node (ref "R16") (pin "2") (pinfunction "2_2") (pintype "passive"))
    )
    (net (code "27") (name "LED_MOT_1") (class "Default")
      (node (ref "IC1") (pin "27") (pinfunction "PD7_27") (pintype "bidirectional"))
      (node (ref "R17") (pin "2") (pinfunction "2_2") (pintype "passive"))
    )
    (net (code "28") (name "LED_MOT_2") (class "Default")
      (node (ref "IC1") (pin "33") (pinfunction "PE3_33") (pintype "bidirectional"))
      (node (ref "R18") (pin "2") (pinfunction "2_2") (pintype "passive"))
    )
    (net (code "29") (name "LED_ORDERS") (class "Default")
      (node (ref "IC1") (pin "24") (pinfunction "PD4_24") (pintype "bidirectional"))
      (node (ref "R14") (pin "2") (pinfunction "2_2") (pintype "passive"))
    )
    (net (code "30") (name "LED_POWER") (class "Default")
      (node (ref "IC1") (pin "23") (pinfunction "PD3_23") (pintype "bidirectional"))
      (node (ref "R13") (pin "2") (pinfunction "2_2") (pintype "passive"))
    )
    (net (code "31") (name "MISO") (class "Default")
      (node (ref "IC1") (pin "16") (pinfunction "PC6_16") (pintype "bidirectional"))
      (node (ref "OK6") (pin "8") (pinfunction "COL_8") (pintype "passive"))
      (node (ref "R4") (pin "1") (pinfunction "1_1") (pintype "passive"))
    )
    (net (code "32") (name "MOSI") (class "Default")
      (node (ref "IC1") (pin "15") (pinfunction "PC5_15") (pintype "bidirectional"))
      (node (ref "OK5") (pin "3") (pinfunction "A_3") (pintype "passive"))
    )
    (net (code "33") (name "MOT_CONTROL_A_1") (class "Default")
      (node (ref "IC1") (pin "13") (pinfunction "PC3_13") (pintype "bidirectional"))
      (node (ref "Q2") (pin "1") (pinfunction "G_1") (pintype "passive"))
      (node (ref "R1") (pin "1") (pinfunction "1_1") (pintype "passive"))
    )
    (net (code "34") (name "MOT_CONTROL_A_2") (class "Default")
      (node (ref "IC1") (pin "7") (pinfunction "PB3_7") (pintype "bidirectional"))
      (node (ref "Q5") (pin "1") (pinfunction "G_1") (pintype "passive"))
      (node (ref "R6") (pin "2") (pinfunction "2_2") (pintype "passive"))
    )
    (net (code "35") (name "MOT_CONTROL_B_1") (class "Default")
      (node (ref "IC1") (pin "14") (pinfunction "PC4_14") (pintype "bidirectional"))
      (node (ref "Q4") (pin "1") (pinfunction "G_1") (pintype "passive"))
      (node (ref "R3") (pin "1") (pinfunction "1_1") (pintype "passive"))
    )
    (net (code "36") (name "MOT_CONTROL_B_2") (class "Default")
      (node (ref "IC1") (pin "5") (pinfunction "PB1_5") (pintype "bidirectional"))
      (node (ref "Q6") (pin "1") (pinfunction "G_1") (pintype "passive"))
      (node (ref "R7") (pin "2") (pinfunction "2_2") (pintype "passive"))
    )
    (net (code "37") (name "MOT_CONTROL_EN_1") (class "Default")
      (node (ref "IC1") (pin "21") (pinfunction "PD1_21") (pintype "bidirectional"))
      (node (ref "Q1") (pin "1") (pinfunction "G_1") (pintype "passive"))
      (node (ref "R33") (pin "1") (pinfunction "1_1") (pintype "passive"))
    )
    (net (code "38") (name "MOT_CONTROL_EN_2") (class "Default")
      (node (ref "IC1") (pin "20") (pinfunction "PD0_20") (pintype "bidirectional"))
      (node (ref "Q3") (pin "1") (pinfunction "G_1") (pintype "passive"))
      (node (ref "R5") (pin "2") (pinfunction "2_2") (pintype "passive"))
    )
    (net (code "39") (name "N$42") (class "Default")
      (node (ref "IC1") (pin "37") (pinfunction "PR1(XT1)_37") (pintype "bidirectional"))
      (node (ref "JP6") (pin "2") (pinfunction "2_2") (pintype "passive"))
    )
    (net (code "40") (name "Net-(IC2-EN1)") (class "Default")
      (node (ref "IC2") (pin "1") (pinfunction "EN1_1") (pintype "bidirectional"))
      (node (ref "LED2") (pin "A") (pinfunction "A_A") (pintype "passive"))
      (node (ref "OK1") (pin "8") (pinfunction "COL_8") (pintype "passive"))
      (node (ref "R21") (pin "2") (pinfunction "2_2") (pintype "passive"))
    )
    (net (code "41") (name "Net-(IC2-EN2)") (class "Default")
      (node (ref "IC2") (pin "9") (pinfunction "EN2_9") (pintype "bidirectional"))
      (node (ref "LED1") (pin "A") (pinfunction "A_A") (pintype "passive"))
      (node (ref "OK2") (pin "6") (pinfunction "COL_6") (pintype "passive"))
      (node (ref "R20") (pin "1") (pinfunction "1_1") (pintype "passive"))
    )
    (net (code "42") (name "Net-(IC2-M1A)") (class "Default")
      (node (ref "IC2") (pin "3") (pinfunction "M1A_3") (pintype "bidirectional"))
      (node (ref "MOTOR_1_OUT") (pin "2") (pinfunction "2_2") (pintype "passive"))
    )
    (net (code "43") (name "Net-(IC2-M1B)") (class "Default")
      (node (ref "IC2") (pin "6") (pinfunction "M1B_6") (pintype "bidirectional"))
      (node (ref "MOTOR_1_OUT") (pin "1") (pinfunction "1_1") (pintype "passive"))
    )
    (net (code "44") (name "Net-(IC2-M2A)") (class "Default")
      (node (ref "IC2") (pin "14") (pinfunction "M2A_14") (pintype "bidirectional"))
      (node (ref "MOTOR_2_OUT") (pin "1") (pinfunction "1_1") (pintype "passive"))
    )
    (net (code "45") (name "Net-(IC2-M2B)") (class "Default")
      (node (ref "IC2") (pin "11") (pinfunction "M2B_11") (pintype "bidirectional"))
      (node (ref "MOTOR_2_OUT") (pin "2") (pinfunction "2_2") (pintype "passive"))
    )
    (net (code "46") (name "Net-(IC2-SIG1A)") (class "Default")
      (node (ref "IC2") (pin "2") (pinfunction "SIG1A_2") (pintype "bidirectional"))
      (node (ref "OK1") (pin "6") (pinfunction "COL_6") (pintype "passive"))
      (node (ref "R19") (pin "1") (pinfunction "1_1") (pintype "passive"))
    )
    (net (code "47") (name "Net-(IC2-SIG1B)") (class "Default")
      (node (ref "IC2") (pin "7") (pinfunction "SIG1B_7") (pintype "bidirectional"))
      (node (ref "OK2") (pin "8") (pinfunction "COL_8") (pintype "passive"))
      (node (ref "R22") (pin "1") (pinfunction "1_1") (pintype "passive"))
    )
    (net (code "48") (name "Net-(IC2-SIG2A)") (class "Default")
      (node (ref "IC2") (pin "15") (pinfunction "SIG2A_15") (pintype "bidirectional"))
      (node (ref "OK3") (pin "8") (pinfunction "COL_8") (pintype "passive"))
      (node (ref "R24") (pin "1") (pinfunction "1_1") (pintype "passive"))
    )
    (net (code "49") (name "Net-(IC2-SIG2B)") (class "Default")
      (node (ref "IC2") (pin "10") (pinfunction "SIG2B_10") (pintype "bidirectional"))
      (node (ref "OK3") (pin "6") (pinfunction "COL_6") (pintype "passive"))
      (node (ref "R23") (pin "1") (pinfunction "1_1") (pintype "passive"))
    )
    (net (code "50") (name "Net-(LED1-PadC)") (class "Default")
      (node (ref "LED1") (pin "C") (pinfunction "C_C") (pintype "passive"))
      (node (ref "R26") (pin "1") (pinfunction "1_1") (pintype "passive"))
    )
    (net (code "51") (name "Net-(LED2-PadC)") (class "Default")
      (node (ref "LED2") (pin "C") (pinfunction "C_C") (pintype "passive"))
      (node (ref "R25") (pin "1") (pinfunction "1_1") (pintype "passive"))
    )
    (net (code "52") (name "Net-(LED3-PadC)") (class "Default")
      (node (ref "LED3") (pin "C") (pinfunction "C_C") (pintype "passive"))
      (node (ref "R32") (pin "1") (pinfunction "1_1") (pintype "passive"))
    )
    (net (code "53") (name "Net-(LED_ERROR1-PadA)") (class "Default")
      (node (ref "LED_ERROR1") (pin "A") (pinfunction "A_A") (pintype "passive"))
      (node (ref "R15") (pin "1") (pinfunction "1_1") (pintype "passive"))
    )
    (net (code "54") (name "Net-(LED_ERROR2-PadA)") (class "Default")
      (node (ref "LED_ERROR2") (pin "A") (pinfunction "A_A") (pintype "passive"))
      (node (ref "R16") (pin "1") (pinfunction "1_1") (pintype "passive"))
    )
    (net (code "55") (name "Net-(LED_MOT1-PadA)") (class "Default")
      (node (ref "LED_MOT1") (pin "A") (pinfunction "A_A") (pintype "passive"))
      (node (ref "R17") (pin "1") (pinfunction "1_1") (pintype "passive"))
    )
    (net (code "56") (name "Net-(LED_MOT2-PadA)") (class "Default")
      (node (ref "LED_MOT2") (pin "A") (pinfunction "A_A") (pintype "passive"))
      (node (ref "R18") (pin "1") (pinfunction "1_1") (pintype "passive"))
    )
    (net (code "57") (name "Net-(LED_ORDERS-PadA)") (class "Default")
      (node (ref "LED_ORDERS") (pin "A") (pinfunction "A_A") (pintype "passive"))
      (node (ref "R14") (pin "1") (pinfunction "1_1") (pintype "passive"))
    )
    (net (code "58") (name "Net-(LED_POWER-PadA)") (class "Default")
      (node (ref "LED_POWER") (pin "A") (pinfunction "A_A") (pintype "passive"))
      (node (ref "R13") (pin "1") (pinfunction "1_1") (pintype "passive"))
    )
    (net (code "59") (name "Net-(OK1A-C)") (class "Default")
      (node (ref "OK1") (pin "2") (pinfunction "C_2") (pintype "passive"))
      (node (ref "Q1") (pin "3") (pinfunction "D_3") (pintype "passive"))
    )
    (net (code "60") (name "Net-(OK1B-C)") (class "Default")
      (node (ref "OK1") (pin "4") (pinfunction "C_4") (pintype "passive"))
      (node (ref "Q2") (pin "3") (pinfunction "D_3") (pintype "passive"))
    )
    (net (code "61") (name "Net-(OK2A-C)") (class "Default")
      (node (ref "OK2") (pin "2") (pinfunction "C_2") (pintype "passive"))
      (node (ref "Q4") (pin "3") (pinfunction "D_3") (pintype "passive"))
    )
    (net (code "62") (name "Net-(OK2B-C)") (class "Default")
      (node (ref "OK2") (pin "4") (pinfunction "C_4") (pintype "passive"))
      (node (ref "Q3") (pin "3") (pinfunction "D_3") (pintype "passive"))
    )
    (net (code "63") (name "Net-(OK3A-C)") (class "Default")
      (node (ref "OK3") (pin "2") (pinfunction "C_2") (pintype "passive"))
      (node (ref "Q5") (pin "3") (pinfunction "D_3") (pintype "passive"))
    )
    (net (code "64") (name "Net-(OK3B-C)") (class "Default")
      (node (ref "OK3") (pin "4") (pinfunction "C_4") (pintype "passive"))
      (node (ref "Q6") (pin "3") (pinfunction "D_3") (pintype "passive"))
    )
    (net (code "65") (name "Net-(OK4A-C)") (class "Default")
      (node (ref "OK4") (pin "2") (pinfunction "C_2") (pintype "passive"))
      (node (ref "R9") (pin "2") (pinfunction "2_2") (pintype "passive"))
    )
    (net (code "66") (name "Net-(OK4B-C)") (class "Default")
      (node (ref "OK4") (pin "4") (pinfunction "C_4") (pintype "passive"))
      (node (ref "R10") (pin "2") (pinfunction "2_2") (pintype "passive"))
    )
    (net (code "67") (name "Net-(OK4B-COL)") (class "Default")
      (node (ref "OK4") (pin "6") (pinfunction "COL_6") (pintype "passive"))
      (node (ref "R31") (pin "1") (pinfunction "1_1") (pintype "passive"))
      (node (ref "SLAVE_SELECT_2") (pin "1") (pinfunction "1_1") (pintype "passive"))
    )
    (net (code "68") (name "Net-(OK5A-C)") (class "Default")
      (node (ref "OK5") (pin "2") (pinfunction "C_2") (pintype "passive"))
      (node (ref "R11") (pin "2") (pinfunction "2_2") (pintype "passive"))
    )
    (net (code "69") (name "Net-(OK5B-C)") (class "Default")
      (node (ref "OK5") (pin "4") (pinfunction "C_4") (pintype "passive"))
      (node (ref "R12") (pin "2") (pinfunction "2_2") (pintype "passive"))
    )
    (net (code "70") (name "Net-(OK6A-A)") (class "Default")
      (node (ref "OK6") (pin "1") (pinfunction "A_1") (pintype "passive"))
      (node (ref "R28") (pin "2") (pinfunction "2_2") (pintype "passive"))
    )
    (net (code "71") (name "Net-(OK6B-A)") (class "Default")
      (node (ref "OK6") (pin "3") (pinfunction "A_3") (pintype "passive"))
      (node (ref "OPTO_IN") (pin "1") (pinfunction "1_1") (pintype "passive"))
    )
    (net (code "72") (name "Net-(OK6B-C)") (class "Default")
      (node (ref "OK6") (pin "4") (pinfunction "C_4") (pintype "passive"))
      (node (ref "OPTO_IN") (pin "2") (pinfunction "2_2") (pintype "passive"))
    )
    (net (code "73") (name "Net-(Q1-S)") (class "Default")
      (node (ref "Q1") (pin "2") (pinfunction "S_2") (pintype "passive"))
      (node (ref "R2") (pin "2") (pinfunction "2_2") (pintype "passive"))
    )
    (net (code "74") (name "Net-(Q2-S)") (class "Default")
      (node (ref "Q2") (pin "2") (pinfunction "S_2") (pintype "passive"))
      (node (ref "R34") (pin "2") (pinfunction "2_2") (pintype "passive"))
    )
    (net (code "75") (name "Net-(Q3-S)") (class "Default")
      (node (ref "Q3") (pin "2") (pinfunction "S_2") (pintype "passive"))
      (node (ref "R35") (pin "2") (pinfunction "2_2") (pintype "passive"))
    )
    (net (code "76") (name "Net-(Q4-S)") (class "Default")
      (node (ref "Q4") (pin "2") (pinfunction "S_2") (pintype "passive"))
      (node (ref "R36") (pin "2") (pinfunction "2_2") (pintype "passive"))
    )
    (net (code "77") (name "Net-(Q5-S)") (class "Default")
      (node (ref "Q5") (pin "2") (pinfunction "S_2") (pintype "passive"))
      (node (ref "R37") (pin "2") (pinfunction "2_2") (pintype "passive"))
    )
    (net (code "78") (name "Net-(Q6-S)") (class "Default")
      (node (ref "Q6") (pin "2") (pinfunction "S_2") (pintype "passive"))
      (node (ref "R38") (pin "2") (pinfunction "2_2") (pintype "passive"))
    )
    (net (code "79") (name "OPTIONAL_OPTO_IN") (class "Default")
      (node (ref "IC1") (pin "36") (pinfunction "PR0(XT2)_36") (pintype "bidirectional"))
      (node (ref "OK6") (pin "6") (pinfunction "COL_6") (pintype "passive"))
      (node (ref "R8") (pin "1") (pinfunction "1_1") (pintype "passive"))
    )
    (net (code "80") (name "PDI_CLK") (class "Default")
      (node (ref "IC1") (pin "35") (pinfunction "~{RESET}/PDI_CLK_35") (pintype "bidirectional"))
      (node (ref "JP3") (pin "2") (pinfunction "2_2") (pintype "passive"))
    )
    (net (code "81") (name "PDI_DATA") (class "Default")
      (node (ref "IC1") (pin "34") (pinfunction "PDI_DATA_34") (pintype "bidirectional"))
      (node (ref "JP3") (pin "6") (pinfunction "6_6") (pintype "passive"))
    )
    (net (code "82") (name "SCK") (class "Default")
      (node (ref "IC1") (pin "17") (pinfunction "PC7_17") (pintype "bidirectional"))
      (node (ref "OK5") (pin "1") (pinfunction "A_1") (pintype "passive"))
    )
    (net (code "83") (name "SCL1") (class "Default")
      (node (ref "I2C1") (pin "1") (pinfunction "1_1") (pintype "passive"))
      (node (ref "IC1") (pin "29") (pinfunction "PE1_29") (pintype "bidirectional"))
      (node (ref "U$1") (pin "A3") (pinfunction "A3_A3") (pintype "bidirectional"))
      (node (ref "U$1") (pin "B3") (pinfunction "B3_B3") (pintype "bidirectional"))
    )
    (net (code "84") (name "SCL2") (class "Default")
      (node (ref "I2C2") (pin "1") (pinfunction "1_1") (pintype "passive"))
      (node (ref "IC1") (pin "11") (pinfunction "PC1_11") (pintype "bidirectional"))
      (node (ref "U$1") (pin "A5") (pinfunction "A5_A5") (pintype "bidirectional"))
      (node (ref "U$1") (pin "B5") (pinfunction "B5_B5") (pintype "bidirectional"))
    )
    (net (code "85") (name "SDA1") (class "Default")
      (node (ref "I2C1") (pin "2") (pinfunction "2_2") (pintype "passive"))
      (node (ref "IC1") (pin "28") (pinfunction "PE0_28") (pintype "bidirectional"))
      (node (ref "U$1") (pin "A4") (pinfunction "A4_A4") (pintype "bidirectional"))
      (node (ref "U$1") (pin "B4") (pinfunction "B4_B4") (pintype "bidirectional"))
    )
    (net (code "86") (name "SDA2") (class "Default")
      (node (ref "I2C2") (pin "2") (pinfunction "2_2") (pintype "passive"))
      (node (ref "IC1") (pin "10") (pinfunction "PC0_10") (pintype "bidirectional"))
      (node (ref "U$1") (pin "A6") (pinfunction "A6_A6") (pintype "bidirectional"))
      (node (ref "U$1") (pin "B6") (pinfunction "B6_B6") (pintype "bidirectional"))
    )
    (net (code "87") (name "SS1") (class "Default")
      (node (ref "IC1") (pin "3") (pinfunction "PA7_3") (pintype "bidirectional"))
      (node (ref "OK4") (pin "3") (pinfunction "A_3") (pintype "passive"))
    )
    (net (code "88") (name "SS2") (class "Default")
      (node (ref "IC1") (pin "4") (pinfunction "PB0_4") (pintype "bidirectional"))
      (node (ref "OK4") (pin "1") (pinfunction "A_1") (pintype "passive"))
    )
    (net (code "89") (name "unconnected-(JP3-Pad3)") (class "Default")
      (node (ref "JP3") (pin "3") (pinfunction "3_3") (pintype "passive"))
    )
    (net (code "90") (name "unconnected-(JP3-Pad4)") (class "Default")
      (node (ref "JP3") (pin "4") (pinfunction "4_4") (pintype "passive"))
    )
    (net (code "91") (name "unconnected-(U$2-NC-Pad5)") (class "Default")
      (node (ref "U$2") (pin "5") (pinfunction "NC_5") (pintype "bidirectional"))
    )
    (net (code "92") (name "unconnected-(U$2-NC2-Pad6)") (class "Default")
      (node (ref "U$2") (pin "6") (pinfunction "NC2_6") (pintype "bidirectional"))
    )
  )
)
